# 1-Schematic_USB_WAVER.net
KiCad netlist of a schematic drawn in EasyEDA
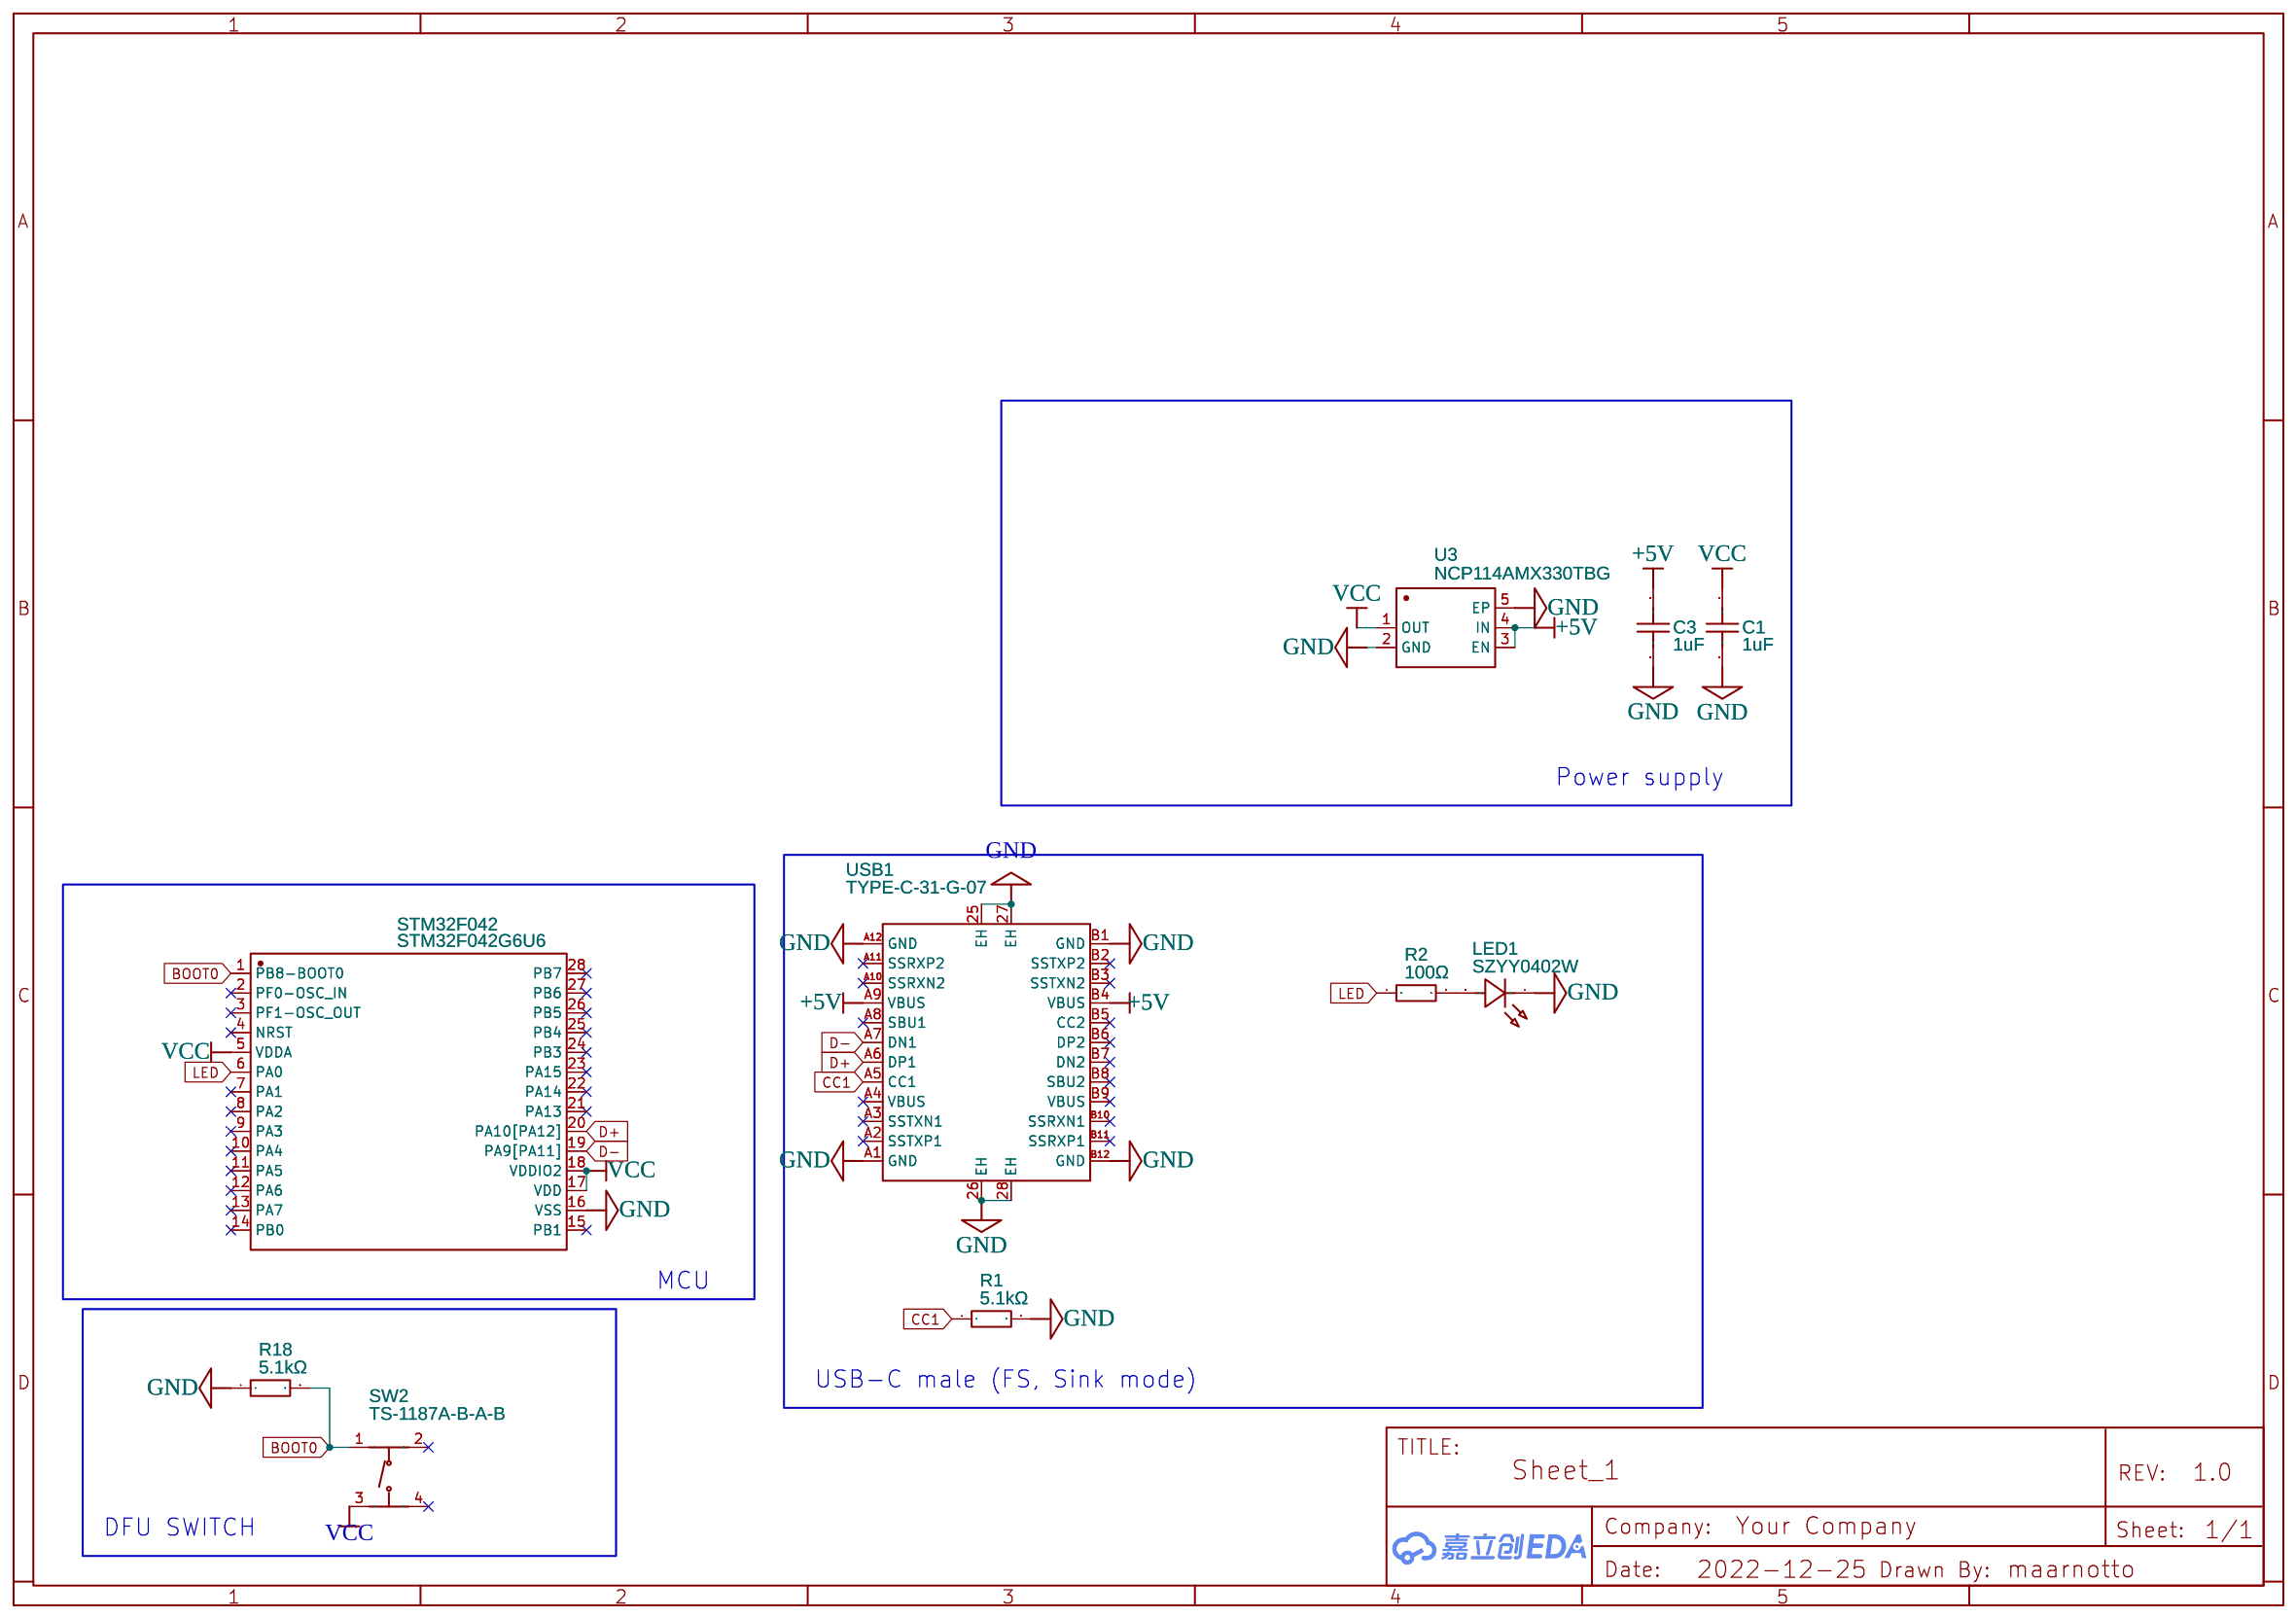
[diagram p0: schematic sheet]

(export (version "E")
  (design (tool "Eeschema 10.0.6"))
  (components
    (comp (ref "C1") (value "1uF") (libsource (lib "") (part "C_0603_US")))
    (comp (ref "C3") (value "1uF") (libsource (lib "") (part "C_0603_US")))
    (comp (ref "LED1")
      (value "SZYY0402W")
      (fields (field (name "Manufacturer") "yongyu(永裕光电)"))
      (libsource (lib "") (part "SZYY0402W"))
    )
    (comp (ref "R1")
      (value "5.1kΩ")
      (fields
        (field (name "Manufacturer Part") "0402WGF5101TCE")
        (field (name "Manufacturer") "UNI-ROYAL(厚声)")
      )
      (libsource (lib "") (part "0402WGF5101TCE"))
    )
    (comp (ref "R2")
      (value "100Ω")
      (fields
        (field (name "Manufacturer Part") "0402WGF1000TCE")
        (field (name "Manufacturer") "UNI-ROYAL(厚声)")
      )
      (libsource (lib "") (part "0402WGF1000TCE"))
    )
    (comp (ref "R18")
      (value "5.1kΩ")
      (fields
        (field (name "Manufacturer Part") "0402WGF5101TCE")
        (field (name "Manufacturer") "UNI-ROYAL(厚声)")
      )
      (libsource (lib "") (part "0402WGF5101TCE"))
    )
    (comp (ref "STM32F042")
      (value "STM32F042G6U6")
      (fields (field (name "Manufacturer") "ST(意法半导体)"))
      (libsource (lib "") (part "STM32F042G6U6"))
    )
    (comp (ref "SW2")
      (value "TS-1187A-B-A-B")
      (fields (field (name "Manufacturer") "XKB Connectivity(中国星坤)"))
      (libsource (lib "") (part "TS-1187A-B-A-B"))
    )
    (comp (ref "U3")
      (value "NCP114AMX330TBG")
      (fields (field (name "Manufacturer") "onsemi(安森美)"))
      (libsource (lib "") (part "NCP114AMX330TBG"))
    )
    (comp (ref "USB1")
      (value "TYPE-C-31-G-07")
      (fields (field (name "Manufacturer") "韩国韩荣"))
      (libsource (lib "") (part "TYPE-C-31-G-07"))
    )
  )
  (nets
    (net (code "1") (name "+5V") (class "Default")
      (node (ref "C3") (pin "2") (pinfunction "2_2") (pintype "unspecified"))
      (node (ref "U3") (pin "3") (pinfunction "EN_3") (pintype "unspecified"))
      (node (ref "U3") (pin "4") (pinfunction "IN_4") (pintype "unspecified"))
      (node (ref "USB1") (pin "A9") (pinfunction "VBUS_A9") (pintype "unspecified"))
      (node (ref "USB1") (pin "B4") (pinfunction "VBUS_B4") (pintype "unspecified"))
    )
    (net (code "2") (name "BOOT0") (class "Default")
      (node (ref "R18") (pin "2") (pinfunction "2_2") (pintype "input"))
      (node (ref "STM32F042") (pin "1") (pinfunction "PB8-BOOT0_1") (pintype "unspecified"))
      (node (ref "SW2") (pin "1") (pinfunction "A_1") (pintype "unspecified"))
    )
    (net (code "3") (name "CC1") (class "Default")
      (node (ref "R1") (pin "1") (pinfunction "1_1") (pintype "input"))
      (node (ref "USB1") (pin "A5") (pinfunction "CC1_A5") (pintype "unspecified"))
    )
    (net (code "4") (name "D+") (class "Default")
      (node (ref "STM32F042") (pin "20") (pinfunction "PA10[PA12]_20") (pintype "unspecified"))
      (node (ref "USB1") (pin "A6") (pinfunction "DP1_A6") (pintype "unspecified"))
    )
    (net (code "5") (name "D-") (class "Default")
      (node (ref "STM32F042") (pin "19") (pinfunction "PA9[PA11]_19") (pintype "unspecified"))
      (node (ref "USB1") (pin "A7") (pinfunction "DN1_A7") (pintype "unspecified"))
    )
    (net (code "6") (name "GND") (class "Default")
      (node (ref "C1") (pin "1") (pinfunction "1_1") (pintype "unspecified"))
      (node (ref "C3") (pin "1") (pinfunction "1_1") (pintype "unspecified"))
      (node (ref "LED1") (pin "1") (pinfunction "K_1") (pintype "unspecified"))
      (node (ref "R1") (pin "2") (pinfunction "2_2") (pintype "input"))
      (node (ref "R18") (pin "1") (pinfunction "1_1") (pintype "input"))
      (node (ref "STM32F042") (pin "16") (pinfunction "VSS_16") (pintype "unspecified"))
      (node (ref "U3") (pin "2") (pinfunction "GND_2") (pintype "unspecified"))
      (node (ref "U3") (pin "5") (pinfunction "EP_5") (pintype "unspecified"))
      (node (ref "USB1") (pin "25") (pinfunction "EH_25") (pintype "unspecified"))
      (node (ref "USB1") (pin "26") (pinfunction "EH_26") (pintype "unspecified"))
      (node (ref "USB1") (pin "27") (pinfunction "EH_27") (pintype "unspecified"))
      (node (ref "USB1") (pin "28") (pinfunction "EH_28") (pintype "unspecified"))
      (node (ref "USB1") (pin "A1") (pinfunction "GND_A1") (pintype "unspecified"))
      (node (ref "USB1") (pin "A12") (pinfunction "GND_A12") (pintype "unspecified"))
      (node (ref "USB1") (pin "B1") (pinfunction "GND_B1") (pintype "unspecified"))
      (node (ref "USB1") (pin "B12") (pinfunction "GND_B12") (pintype "unspecified"))
    )
    (net (code "7") (name "LED") (class "Default")
      (node (ref "R2") (pin "1") (pinfunction "1_1") (pintype "input"))
      (node (ref "STM32F042") (pin "6") (pinfunction "PA0_6") (pintype "unspecified"))
    )
    (net (code "8") (name "Net-(LED1-A)") (class "Default")
      (node (ref "LED1") (pin "2") (pinfunction "A_2") (pintype "unspecified"))
      (node (ref "R2") (pin "2") (pinfunction "2_2") (pintype "input"))
    )
    (net (code "9") (name "VCC") (class "Default")
      (node (ref "C1") (pin "2") (pinfunction "2_2") (pintype "unspecified"))
      (node (ref "STM32F042") (pin "17") (pinfunction "VDD_17") (pintype "unspecified"))
      (node (ref "STM32F042") (pin "18") (pinfunction "VDDIO2_18") (pintype "unspecified"))
      (node (ref "STM32F042") (pin "5") (pinfunction "VDDA_5") (pintype "unspecified"))
      (node (ref "SW2") (pin "3") (pinfunction "C_3") (pintype "unspecified"))
      (node (ref "U3") (pin "1") (pinfunction "OUT_1") (pintype "unspecified"))
    )
    (net (code "10") (name "unconnected-(STM32F042-NRST-Pad4)") (class "Default")
      (node (ref "STM32F042") (pin "4") (pinfunction "NRST_4") (pintype "unspecified+no_connect"))
    )
    (net (code "11") (name "unconnected-(STM32F042-PA1-Pad7)") (class "Default")
      (node (ref "STM32F042") (pin "7") (pinfunction "PA1_7") (pintype "unspecified+no_connect"))
    )
    (net (code "12") (name "unconnected-(STM32F042-PA2-Pad8)") (class "Default")
      (node (ref "STM32F042") (pin "8") (pinfunction "PA2_8") (pintype "unspecified+no_connect"))
    )
    (net (code "13") (name "unconnected-(STM32F042-PA3-Pad9)") (class "Default")
      (node (ref "STM32F042") (pin "9") (pinfunction "PA3_9") (pintype "unspecified+no_connect"))
    )
    (net (code "14") (name "unconnected-(STM32F042-PA4-Pad10)") (class "Default")
      (node (ref "STM32F042") (pin "10") (pinfunction "PA4_10") (pintype "unspecified+no_connect"))
    )
    (net (code "15") (name "unconnected-(STM32F042-PA5-Pad11)") (class "Default")
      (node (ref "STM32F042") (pin "11") (pinfunction "PA5_11") (pintype "unspecified+no_connect"))
    )
    (net (code "16") (name "unconnected-(STM32F042-PA6-Pad12)") (class "Default")
      (node (ref "STM32F042") (pin "12") (pinfunction "PA6_12") (pintype "unspecified+no_connect"))
    )
    (net (code "17") (name "unconnected-(STM32F042-PA7-Pad13)") (class "Default")
      (node (ref "STM32F042") (pin "13") (pinfunction "PA7_13") (pintype "unspecified+no_connect"))
    )
    (net (code "18") (name "unconnected-(STM32F042-PA13-Pad21)") (class "Default")
      (node (ref "STM32F042") (pin "21") (pinfunction "PA13_21") (pintype "unspecified+no_connect"))
    )
    (net (code "19") (name "unconnected-(STM32F042-PA14-Pad22)") (class "Default")
      (node (ref "STM32F042") (pin "22") (pinfunction "PA14_22") (pintype "unspecified+no_connect"))
    )
    (net (code "20") (name "unconnected-(STM32F042-PA15-Pad23)") (class "Default")
      (node (ref "STM32F042") (pin "23") (pinfunction "PA15_23") (pintype "unspecified+no_connect"))
    )
    (net (code "21") (name "unconnected-(STM32F042-PB0-Pad14)") (class "Default")
      (node (ref "STM32F042") (pin "14") (pinfunction "PB0_14") (pintype "unspecified+no_connect"))
    )
    (net (code "22") (name "unconnected-(STM32F042-PB1-Pad15)") (class "Default")
      (node (ref "STM32F042") (pin "15") (pinfunction "PB1_15") (pintype "unspecified+no_connect"))
    )
    (net (code "23") (name "unconnected-(STM32F042-PB3-Pad24)") (class "Default")
      (node (ref "STM32F042") (pin "24") (pinfunction "PB3_24") (pintype "unspecified+no_connect"))
    )
    (net (code "24") (name "unconnected-(STM32F042-PB4-Pad25)") (class "Default")
      (node (ref "STM32F042") (pin "25") (pinfunction "PB4_25") (pintype "unspecified+no_connect"))
    )
    (net (code "25") (name "unconnected-(STM32F042-PB5-Pad26)") (class "Default")
      (node (ref "STM32F042") (pin "26") (pinfunction "PB5_26") (pintype "unspecified+no_connect"))
    )
    (net (code "26") (name "unconnected-(STM32F042-PB6-Pad27)") (class "Default")
      (node (ref "STM32F042") (pin "27") (pinfunction "PB6_27") (pintype "unspecified+no_connect"))
    )
    (net (code "27") (name "unconnected-(STM32F042-PB7-Pad28)") (class "Default")
      (node (ref "STM32F042") (pin "28") (pinfunction "PB7_28") (pintype "unspecified+no_connect"))
    )
    (net (code "28") (name "unconnected-(STM32F042-PF0-OSC_IN-Pad2)") (class "Default")
      (node (ref "STM32F042") (pin "2") (pinfunction "PF0-OSC_IN_2") (pintype "unspecified+no_connect"))
    )
    (net (code "29") (name "unconnected-(STM32F042-PF1-OSC_OUT-Pad3)") (class "Default")
      (node (ref "STM32F042") (pin "3") (pinfunction "PF1-OSC_OUT_3") (pintype "unspecified+no_connect"))
    )
    (net (code "30") (name "unconnected-(SW2-B-Pad2)") (class "Default")
      (node (ref "SW2") (pin "2") (pinfunction "B_2") (pintype "unspecified+no_connect"))
    )
    (net (code "31") (name "unconnected-(SW2-D-Pad4)") (class "Default")
      (node (ref "SW2") (pin "4") (pinfunction "D_4") (pintype "unspecified+no_connect"))
    )
    (net (code "32") (name "unconnected-(USB1-CC2-PadB5)") (class "Default")
      (node (ref "USB1") (pin "B5") (pinfunction "CC2_B5") (pintype "unspecified+no_connect"))
    )
    (net (code "33") (name "unconnected-(USB1-DN2-PadB7)") (class "Default")
      (node (ref "USB1") (pin "B7") (pinfunction "DN2_B7") (pintype "unspecified+no_connect"))
    )
    (net (code "34") (name "unconnected-(USB1-DP2-PadB6)") (class "Default")
      (node (ref "USB1") (pin "B6") (pinfunction "DP2_B6") (pintype "unspecified+no_connect"))
    )
    (net (code "35") (name "unconnected-(USB1-SBU1-PadA8)") (class "Default")
      (node (ref "USB1") (pin "A8") (pinfunction "SBU1_A8") (pintype "unspecified+no_connect"))
    )
    (net (code "36") (name "unconnected-(USB1-SBU2-PadB8)") (class "Default")
      (node (ref "USB1") (pin "B8") (pinfunction "SBU2_B8") (pintype "unspecified+no_connect"))
    )
    (net (code "37") (name "unconnected-(USB1-SSRXN1-PadB10)") (class "Default")
      (node (ref "USB1") (pin "B10") (pinfunction "SSRXN1_B10") (pintype "unspecified+no_connect"))
    )
    (net (code "38") (name "unconnected-(USB1-SSRXN2-PadA10)") (class "Default")
      (node (ref "USB1") (pin "A10") (pinfunction "SSRXN2_A10") (pintype "unspecified+no_connect"))
    )
    (net (code "39") (name "unconnected-(USB1-SSRXP1-PadB11)") (class "Default")
      (node (ref "USB1") (pin "B11") (pinfunction "SSRXP1_B11") (pintype "unspecified+no_connect"))
    )
    (net (code "40") (name "unconnected-(USB1-SSRXP2-PadA11)") (class "Default")
      (node (ref "USB1") (pin "A11") (pinfunction "SSRXP2_A11") (pintype "unspecified+no_connect"))
    )
    (net (code "41") (name "unconnected-(USB1-SSTXN1-PadA3)") (class "Default")
      (node (ref "USB1") (pin "A3") (pinfunction "SSTXN1_A3") (pintype "unspecified+no_connect"))
    )
    (net (code "42") (name "unconnected-(USB1-SSTXN2-PadB3)") (class "Default")
      (node (ref "USB1") (pin "B3") (pinfunction "SSTXN2_B3") (pintype "unspecified+no_connect"))
    )
    (net (code "43") (name "unconnected-(USB1-SSTXP1-PadA2)") (class "Default")
      (node (ref "USB1") (pin "A2") (pinfunction "SSTXP1_A2") (pintype "unspecified+no_connect"))
    )
    (net (code "44") (name "unconnected-(USB1-SSTXP2-PadB2)") (class "Default")
      (node (ref "USB1") (pin "B2") (pinfunction "SSTXP2_B2") (pintype "unspecified+no_connect"))
    )
    (net (code "45") (name "unconnected-(USB1-VBUS-PadA4)") (class "Default")
      (node (ref "USB1") (pin "A4") (pinfunction "VBUS_A4") (pintype "unspecified+no_connect"))
    )
    (net (code "46") (name "unconnected-(USB1-VBUS-PadB9)") (class "Default")
      (node (ref "USB1") (pin "B9") (pinfunction "VBUS_B9") (pintype "unspecified+no_connect"))
    )
  )
)
